# EncoderInterface_J007399_T4.net
KiCad netlist of a schematic drawn in EAGLE
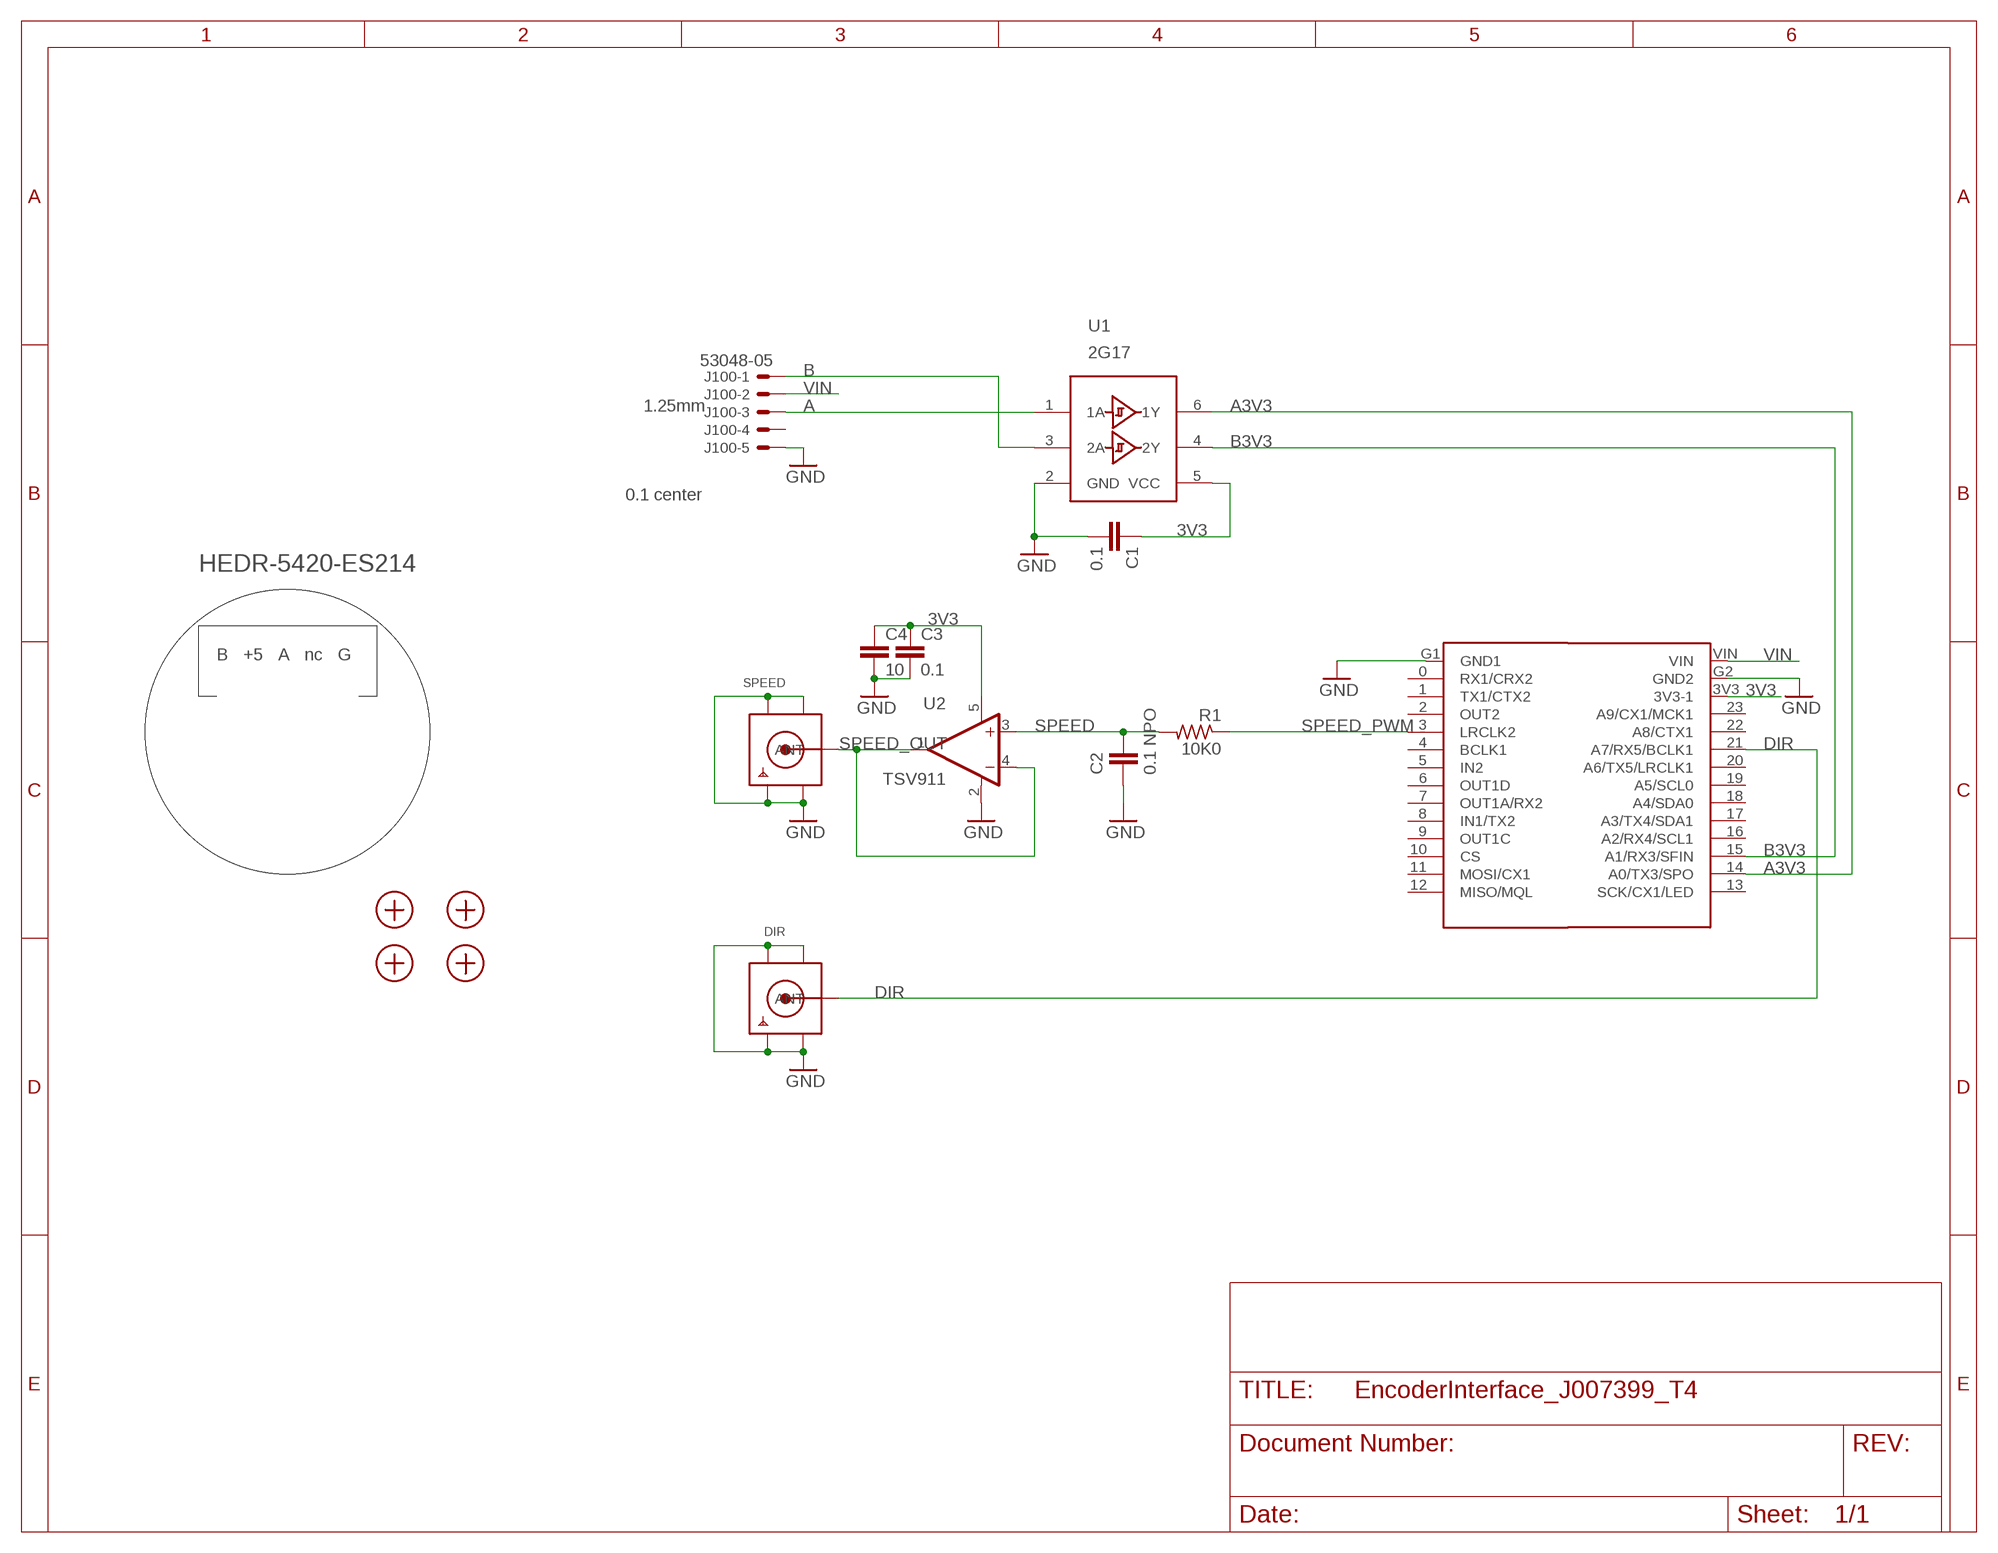
[diagram p0: schematic, sheet 1]

(export (version "E")
  (design (tool "Eeschema 10.0.6"))
  (components
    (comp (ref "C1")
      (value "0.1")
      (footprint "eagle-import:0603S")
      (libsource (lib "eagle-import") (part "CAPS0603S"))
    )
    (comp (ref "C2")
      (value "0.1 NPO")
      (footprint "eagle-import:1206S")
      (libsource (lib "eagle-import") (part "CAPS1206S"))
    )
    (comp (ref "C3")
      (value "0.1")
      (footprint "eagle-import:0603S")
      (libsource (lib "eagle-import") (part "CAPS0603S"))
    )
    (comp (ref "C4")
      (value "10")
      (footprint "eagle-import:1206S")
      (libsource (lib "eagle-import") (part "CAPS1206S"))
    )
    (comp (ref "DIR")
      (value "SMACONNECTOR")
      (footprint "eagle-import:SMA90_DIP")
      (libsource (lib "eagle-import") (part "SMACONNECTOR"))
    )
    (comp (ref "J100")
      (value "53048-05")
      (footprint "eagle-import:53048-05")
      (fields (field (name "MF") "MOLEX") (field (name "MPN") "53048-0510"))
      (libsource (lib "eagle-import") (part "53?-05048"))
    )
    (comp (ref "M1A")
      (value "TEENSY40A")
      (footprint "eagle-import:TEENSY40-A")
      (libsource (lib "eagle-import") (part "TEENSY40A"))
    )
    (comp (ref "M1B")
      (value "TEENSY40B")
      (footprint "eagle-import:TEENSY40-B")
      (libsource (lib "eagle-import") (part "TEENSY40B"))
    )
    (comp (ref "R1")
      (value "10K0")
      (footprint "eagle-import:0805S")
      (libsource (lib "eagle-import") (part "RESISTOR_SM0805S"))
    )
    (comp (ref "S1")
      (value "SCREW2-56SCREW")
      (footprint "eagle-import:2-56SOCKET")
      (libsource (lib "eagle-import") (part "SCREW2-56SCREW"))
    )
    (comp (ref "S2")
      (value "SCREW2-56SCREW")
      (footprint "eagle-import:2-56SOCKET")
      (libsource (lib "eagle-import") (part "SCREW2-56SCREW"))
    )
    (comp (ref "S3")
      (value "SCREW2-56SCREW")
      (footprint "eagle-import:2-56SOCKET")
      (libsource (lib "eagle-import") (part "SCREW2-56SCREW"))
    )
    (comp (ref "S4")
      (value "SCREW2-56SCREW")
      (footprint "eagle-import:2-56SOCKET")
      (libsource (lib "eagle-import") (part "SCREW2-56SCREW"))
    )
    (comp (ref "SPEED")
      (value "SMACONNECTOR")
      (footprint "eagle-import:SMA90_DIP")
      (libsource (lib "eagle-import") (part "SMACONNECTOR"))
    )
    (comp (ref "U1")
      (value "2G17")
      (footprint "eagle-import:SOT23-6")
      (libsource (lib "eagle-import") (part "2G17"))
    )
    (comp (ref "U2")
      (value "TSV911")
      (footprint "eagle-import:SOT23-5")
      (fields (field (name "MF") "TEXAS INSTRUMENTS") (field (name "MPN") "OPA237NA/250"))
      (libsource (lib "eagle-import") (part "OPA237N"))
    )
  )
  (nets
    (net (code "1") (name "/3V3") (class "Default")
      (node (ref "C1") (pin "1") (pinfunction "1_1") (pintype "passive"))
      (node (ref "C3") (pin "1") (pinfunction "1_1") (pintype "passive"))
      (node (ref "C4") (pin "1") (pinfunction "1_1") (pintype "passive"))
      (node (ref "M1B") (pin "3V3") (pinfunction "3V3-1_3V3") (pintype "bidirectional"))
      (node (ref "U1") (pin "5") (pinfunction "VCC_5") (pintype "bidirectional"))
      (node (ref "U2") (pin "5") (pinfunction "V+_5") (pintype "power_in"))
    )
    (net (code "2") (name "/A") (class "Default")
      (node (ref "J100") (pin "3") (pinfunction "S_3") (pintype "passive"))
      (node (ref "U1") (pin "1") (pinfunction "1A_1") (pintype "bidirectional"))
    )
    (net (code "3") (name "/A3V3") (class "Default")
      (node (ref "M1B") (pin "14") (pinfunction "A0/TX3/SPO_14") (pintype "bidirectional"))
      (node (ref "U1") (pin "6") (pinfunction "1Y_6") (pintype "bidirectional"))
    )
    (net (code "4") (name "/B") (class "Default")
      (node (ref "J100") (pin "1") (pinfunction "S_1") (pintype "passive"))
      (node (ref "U1") (pin "3") (pinfunction "2A_3") (pintype "bidirectional"))
    )
    (net (code "5") (name "/B3V3") (class "Default")
      (node (ref "M1B") (pin "15") (pinfunction "A1/RX3/SFIN_15") (pintype "bidirectional"))
      (node (ref "U1") (pin "4") (pinfunction "2Y_4") (pintype "bidirectional"))
    )
    (net (code "6") (name "/DIR") (class "Default")
      (node (ref "DIR") (pin "ANTENNA") (pinfunction "ANT_ANTENNA") (pintype "bidirectional"))
      (node (ref "M1B") (pin "21") (pinfunction "A7/RX5/BCLK1_21") (pintype "bidirectional"))
    )
    (net (code "7") (name "/SPEED") (class "Default")
      (node (ref "C2") (pin "1") (pinfunction "1_1") (pintype "passive"))
      (node (ref "R1") (pin "2") (pinfunction "2_2") (pintype "passive"))
      (node (ref "U2") (pin "3") (pinfunction "+IN_3") (pintype "input"))
    )
    (net (code "8") (name "/SPEED_OUT") (class "Default")
      (node (ref "SPEED") (pin "ANTENNA") (pinfunction "ANT_ANTENNA") (pintype "bidirectional"))
      (node (ref "U2") (pin "1") (pinfunction "OUT_1") (pintype "output"))
      (node (ref "U2") (pin "4") (pinfunction "-IN_4") (pintype "input"))
    )
    (net (code "9") (name "/SPEED_PWM") (class "Default")
      (node (ref "M1A") (pin "3") (pinfunction "LRCLK2_3") (pintype "bidirectional"))
      (node (ref "R1") (pin "1") (pinfunction "1_1") (pintype "passive"))
    )
    (net (code "10") (name "/VIN") (class "Default")
      (node (ref "J100") (pin "2") (pinfunction "S_2") (pintype "passive"))
      (node (ref "M1B") (pin "VIN") (pinfunction "VIN_VIN") (pintype "bidirectional"))
    )
    (net (code "11") (name "GND") (class "Default")
      (node (ref "C1") (pin "2") (pinfunction "2_2") (pintype "passive"))
      (node (ref "C2") (pin "2") (pinfunction "2_2") (pintype "passive"))
      (node (ref "C3") (pin "2") (pinfunction "2_2") (pintype "passive"))
      (node (ref "C4") (pin "2") (pinfunction "2_2") (pintype "passive"))
      (node (ref "DIR") (pin "GND1") (pinfunction "GND1_GND1") (pintype "power_in"))
      (node (ref "DIR") (pin "GND2") (pinfunction "GND2_GND2") (pintype "power_in"))
      (node (ref "DIR") (pin "GND3") (pinfunction "GND3_GND3") (pintype "power_in"))
      (node (ref "DIR") (pin "GND4") (pinfunction "GND4_GND4") (pintype "power_in"))
      (node (ref "J100") (pin "5") (pinfunction "S_5") (pintype "passive"))
      (node (ref "M1A") (pin "G1") (pinfunction "GND1_G1") (pintype "bidirectional"))
      (node (ref "M1B") (pin "G2") (pinfunction "GND2_G2") (pintype "bidirectional"))
      (node (ref "SPEED") (pin "GND1") (pinfunction "GND1_GND1") (pintype "power_in"))
      (node (ref "SPEED") (pin "GND2") (pinfunction "GND2_GND2") (pintype "power_in"))
      (node (ref "SPEED") (pin "GND3") (pinfunction "GND3_GND3") (pintype "power_in"))
      (node (ref "SPEED") (pin "GND4") (pinfunction "GND4_GND4") (pintype "power_in"))
      (node (ref "U1") (pin "2") (pinfunction "GND_2") (pintype "bidirectional"))
      (node (ref "U2") (pin "2") (pinfunction "V-_2") (pintype "power_in"))
    )
    (net (code "12") (name "unconnected-(J100D-S-Pad4)") (class "Default")
      (node (ref "J100") (pin "4") (pinfunction "S_4") (pintype "passive"))
    )
    (net (code "13") (name "unconnected-(M1A-BCLK1-Pad4)") (class "Default")
      (node (ref "M1A") (pin "4") (pinfunction "BCLK1_4") (pintype "bidirectional"))
    )
    (net (code "14") (name "unconnected-(M1A-CS-Pad10)") (class "Default")
      (node (ref "M1A") (pin "10") (pinfunction "CS_10") (pintype "bidirectional"))
    )
    (net (code "15") (name "unconnected-(M1A-IN1{slash}TX2-Pad8)") (class "Default")
      (node (ref "M1A") (pin "8") (pinfunction "IN1/TX2_8") (pintype "bidirectional"))
    )
    (net (code "16") (name "unconnected-(M1A-IN2-Pad5)") (class "Default")
      (node (ref "M1A") (pin "5") (pinfunction "IN2_5") (pintype "bidirectional"))
    )
    (net (code "17") (name "unconnected-(M1A-MISO{slash}MQL-Pad12)") (class "Default")
      (node (ref "M1A") (pin "12") (pinfunction "MISO/MQL_12") (pintype "bidirectional"))
    )
    (net (code "18") (name "unconnected-(M1A-MOSI{slash}CX1-Pad11)") (class "Default")
      (node (ref "M1A") (pin "11") (pinfunction "MOSI/CX1_11") (pintype "bidirectional"))
    )
    (net (code "19") (name "unconnected-(M1A-OUT1A{slash}RX2-Pad7)") (class "Default")
      (node (ref "M1A") (pin "7") (pinfunction "OUT1A/RX2_7") (pintype "bidirectional"))
    )
    (net (code "20") (name "unconnected-(M1A-OUT1C-Pad9)") (class "Default")
      (node (ref "M1A") (pin "9") (pinfunction "OUT1C_9") (pintype "bidirectional"))
    )
    (net (code "21") (name "unconnected-(M1A-OUT1D-Pad6)") (class "Default")
      (node (ref "M1A") (pin "6") (pinfunction "OUT1D_6") (pintype "bidirectional"))
    )
    (net (code "22") (name "unconnected-(M1A-OUT2-Pad2)") (class "Default")
      (node (ref "M1A") (pin "2") (pinfunction "OUT2_2") (pintype "bidirectional"))
    )
    (net (code "23") (name "unconnected-(M1A-RX1{slash}CRX2-Pad0)") (class "Default")
      (node (ref "M1A") (pin "0") (pinfunction "RX1/CRX2_0") (pintype "bidirectional"))
    )
    (net (code "24") (name "unconnected-(M1A-TX1{slash}CTX2-Pad1)") (class "Default")
      (node (ref "M1A") (pin "1") (pinfunction "TX1/CTX2_1") (pintype "bidirectional"))
    )
    (net (code "25") (name "unconnected-(M1B-A2{slash}RX4{slash}SCL1-Pad16)") (class "Default")
      (node (ref "M1B") (pin "16") (pinfunction "A2/RX4/SCL1_16") (pintype "bidirectional"))
    )
    (net (code "26") (name "unconnected-(M1B-A3{slash}TX4{slash}SDA1-Pad17)") (class "Default")
      (node (ref "M1B") (pin "17") (pinfunction "A3/TX4/SDA1_17") (pintype "bidirectional"))
    )
    (net (code "27") (name "unconnected-(M1B-A4{slash}SDA0-Pad18)") (class "Default")
      (node (ref "M1B") (pin "18") (pinfunction "A4/SDA0_18") (pintype "bidirectional"))
    )
    (net (code "28") (name "unconnected-(M1B-A5{slash}SCL0-Pad19)") (class "Default")
      (node (ref "M1B") (pin "19") (pinfunction "A5/SCL0_19") (pintype "bidirectional"))
    )
    (net (code "29") (name "unconnected-(M1B-A6{slash}TX5{slash}LRCLK1-Pad20)") (class "Default")
      (node (ref "M1B") (pin "20") (pinfunction "A6/TX5/LRCLK1_20") (pintype "bidirectional"))
    )
    (net (code "30") (name "unconnected-(M1B-A8{slash}CTX1-Pad22)") (class "Default")
      (node (ref "M1B") (pin "22") (pinfunction "A8/CTX1_22") (pintype "bidirectional"))
    )
    (net (code "31") (name "unconnected-(M1B-A9{slash}CX1{slash}MCK1-Pad23)") (class "Default")
      (node (ref "M1B") (pin "23") (pinfunction "A9/CX1/MCK1_23") (pintype "bidirectional"))
    )
    (net (code "32") (name "unconnected-(M1B-SCK{slash}CX1{slash}LED-Pad13)") (class "Default")
      (node (ref "M1B") (pin "13") (pinfunction "SCK/CX1/LED_13") (pintype "bidirectional"))
    )
  )
)
